# OpenMV.net
KiCad netlist of a schematic drawn in Altium Designer
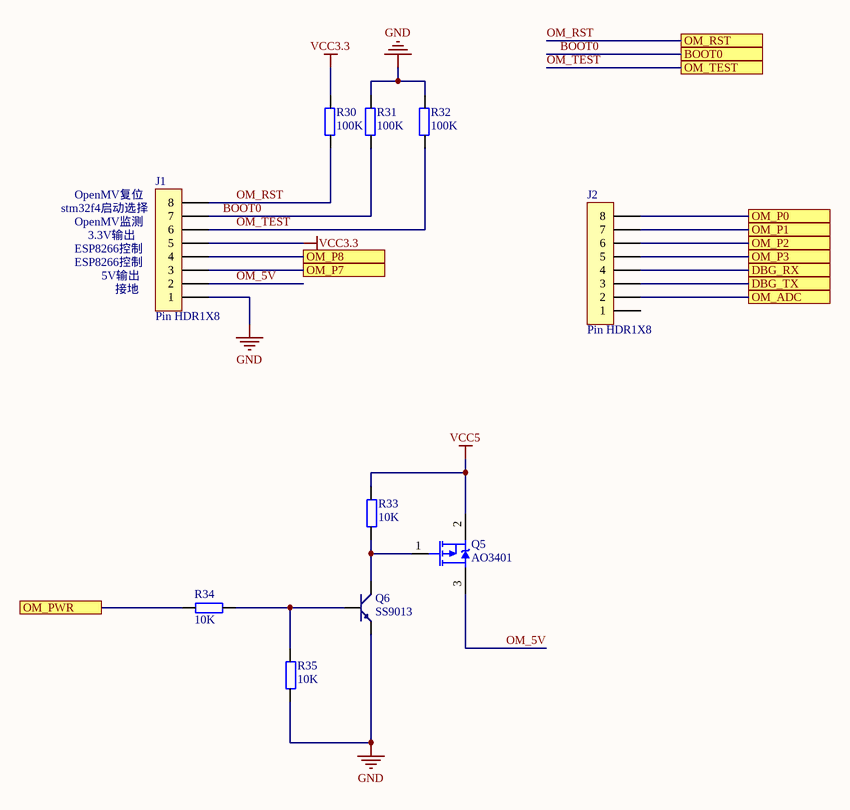
[diagram p0: OpenMV.SchDoc]

(export (version "E")
  (design (tool "Eeschema 10.0.6"))
  (components
    (comp (ref "J1")
      (value "Pin HDR1X8")
      (footprint "Pin HDR1X8/2.54mm-S")
      (libsource (lib "排针") (part "Pin HDR1X8"))
    )
    (comp (ref "J2")
      (value "Pin HDR1X8")
      (footprint "Pin HDR1X8/2.54mm-S")
      (libsource (lib "排针") (part "Pin HDR1X8"))
    )
    (comp (ref "Q5")
      (value "AO3401")
      (footprint "RoboFly:SOT23-3M")
      (description "MOS管_P沟道")
      (fields (field (name "PUBLISHER") "Altium Limited"))
      (libsource (lib "RoboFly") (part "MOSFET-P"))
    )
    (comp (ref "Q6")
      (value "SS9013")
      (footprint "SOT-23R")
      (description "8050/BCW846/BCW847")
      (libsource (lib "Explorer STM32F407封装库") (part "NPN"))
    )
    (comp (ref "R30") (value "100K") (footprint "0603P") (libsource (lib "Explorer STM32F407封装库") (part "R")))
    (comp (ref "R31") (value "100K") (footprint "0603P") (libsource (lib "Explorer STM32F407封装库") (part "R")))
    (comp (ref "R32") (value "100K") (footprint "0603P") (libsource (lib "Explorer STM32F407封装库") (part "R")))
    (comp (ref "R33") (value "10K") (footprint "0603P") (libsource (lib "Explorer STM32F407封装库") (part "R")))
    (comp (ref "R34") (value "10K") (footprint "0603P") (libsource (lib "Explorer STM32F407封装库") (part "R")))
    (comp (ref "R35") (value "10K") (footprint "0603P") (libsource (lib "Explorer STM32F407封装库") (part "R")))
  )
  (nets
    (net (code "1") (name "/BOOT0") (class "Default")
      (node (ref "J1") (pin "7") (pinfunction "7_7") (pintype "passive"))
      (node (ref "R31") (pin "2") (pintype "passive"))
    )
    (net (code "2") (name "/DBG_RX") (class "Default")
      (node (ref "J2") (pin "4") (pinfunction "4_4") (pintype "passive"))
    )
    (net (code "3") (name "/DBG_TX") (class "Default")
      (node (ref "J2") (pin "3") (pinfunction "3_3") (pintype "passive"))
    )
    (net (code "4") (name "/OM_5V") (class "Default")
      (node (ref "J1") (pin "2") (pinfunction "2_2") (pintype "passive"))
      (node (ref "Q5") (pin "3") (pinfunction "D_3") (pintype "passive"))
    )
    (net (code "5") (name "/OM_ADC") (class "Default")
      (node (ref "J2") (pin "2") (pinfunction "2_2") (pintype "passive"))
    )
    (net (code "6") (name "/OM_P0") (class "Default")
      (node (ref "J2") (pin "8") (pinfunction "8_8") (pintype "passive"))
    )
    (net (code "7") (name "/OM_P1") (class "Default")
      (node (ref "J2") (pin "7") (pinfunction "7_7") (pintype "passive"))
    )
    (net (code "8") (name "/OM_P2") (class "Default")
      (node (ref "J2") (pin "6") (pinfunction "6_6") (pintype "passive"))
    )
    (net (code "9") (name "/OM_P3") (class "Default")
      (node (ref "J2") (pin "5") (pinfunction "5_5") (pintype "passive"))
    )
    (net (code "10") (name "/OM_P7") (class "Default")
      (node (ref "J1") (pin "3") (pinfunction "3_3") (pintype "passive"))
    )
    (net (code "11") (name "/OM_P8") (class "Default")
      (node (ref "J1") (pin "4") (pinfunction "4_4") (pintype "passive"))
    )
    (net (code "12") (name "/OM_PWR") (class "Default") (node (ref "R34") (pin "1") (pintype "passive")))
    (net (code "13") (name "/OM_RST") (class "Default")
      (node (ref "J1") (pin "8") (pinfunction "8_8") (pintype "passive"))
      (node (ref "R30") (pin "2") (pintype "passive"))
    )
    (net (code "14") (name "/OM_TEST") (class "Default")
      (node (ref "J1") (pin "6") (pinfunction "6_6") (pintype "passive"))
      (node (ref "R32") (pin "2") (pintype "passive"))
    )
    (net (code "15") (name "GND") (class "Default")
      (node (ref "J1") (pin "1") (pinfunction "1_1") (pintype "passive"))
      (node (ref "Q6") (pin "1") (pinfunction "E_1") (pintype "passive"))
      (node (ref "R31") (pin "1") (pintype "passive"))
      (node (ref "R32") (pin "1") (pintype "passive"))
      (node (ref "R35") (pin "1") (pintype "passive"))
    )
    (net (code "16") (name "Net-(Q5-G)") (class "Default")
      (node (ref "Q5") (pin "1") (pinfunction "G_1") (pintype "passive"))
      (node (ref "Q6") (pin "3") (pinfunction "C_3") (pintype "passive"))
      (node (ref "R33") (pin "1") (pintype "passive"))
    )
    (net (code "17") (name "Net-(Q6-B)") (class "Default")
      (node (ref "Q6") (pin "2") (pinfunction "B_2") (pintype "passive"))
      (node (ref "R34") (pin "2") (pintype "passive"))
      (node (ref "R35") (pin "2") (pintype "passive"))
    )
    (net (code "18") (name "VCC3.3") (class "Default")
      (node (ref "J1") (pin "5") (pinfunction "5_5") (pintype "passive"))
      (node (ref "R30") (pin "1") (pintype "passive"))
    )
    (net (code "19") (name "VCC5") (class "Default")
      (node (ref "Q5") (pin "2") (pinfunction "S_2") (pintype "passive"))
      (node (ref "R33") (pin "2") (pintype "passive"))
    )
    (net (code "20") (name "unconnected-(J2-Pad1)") (class "Default")
      (node (ref "J2") (pin "1") (pinfunction "1_1") (pintype "passive"))
    )
  )
)
